# Ethernet.net
KiCad netlist of a schematic drawn in Altium Designer
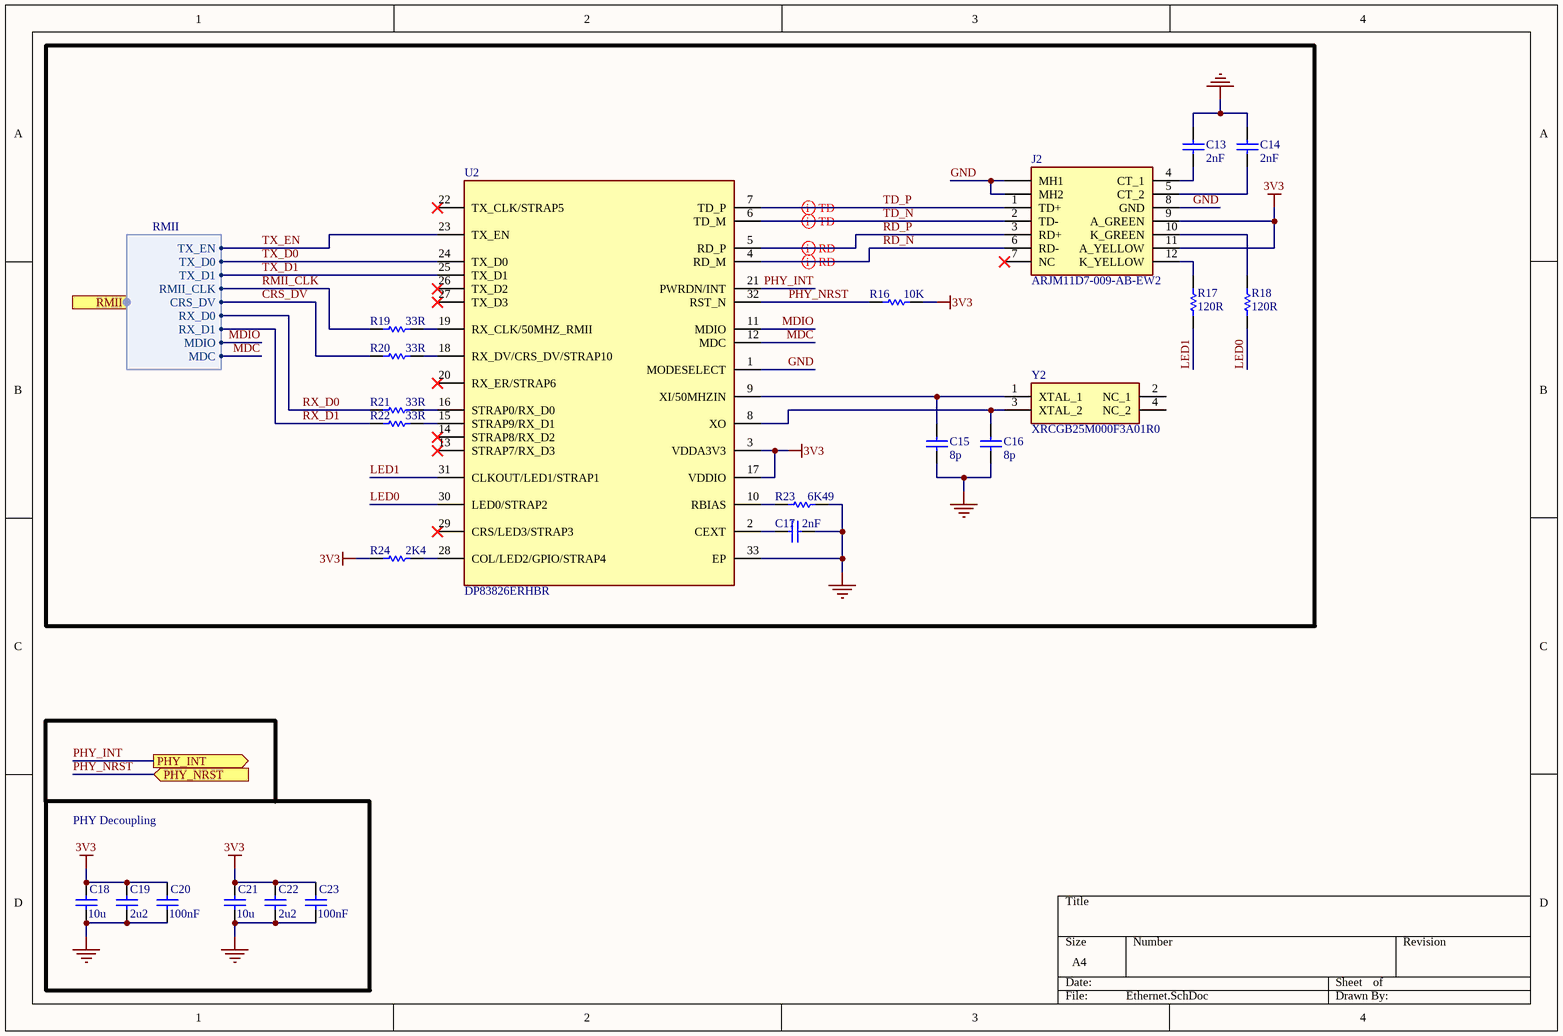
[diagram p0: Ethernet.SchDoc]

(export (version "E")
  (design (tool "Eeschema 10.0.6"))
  (components
    (comp (ref "C13")
      (value "2nF")
      (footprint "0603")
      (description "Capacitor 50V \r\n0603")
      (libsource (lib "Schlib1") (part "C0603C202J5GACTU"))
    )
    (comp (ref "C14")
      (value "2nF")
      (footprint "0603")
      (description "Capacitor 50V \r\n0603")
      (libsource (lib "Schlib1") (part "C0603C202J5GACTU"))
    )
    (comp (ref "C15")
      (value "8p")
      (footprint "0603")
      (description "Capacitor 25V \r\n0603")
      (libsource (lib "Schlib1") (part "06033A8R0DAT2A"))
    )
    (comp (ref "C16")
      (value "8p")
      (footprint "0603")
      (description "Capacitor 25V \r\n0603")
      (libsource (lib "Schlib1") (part "06033A8R0DAT2A"))
    )
    (comp (ref "C17")
      (value "2nF")
      (footprint "0603")
      (description "Capacitor 50V \r\n0603")
      (libsource (lib "Schlib1") (part "C0603C202J5GACTU"))
    )
    (comp (ref "C18")
      (value "10u")
      (footprint "1206")
      (description "Capacitor 50V\r\n1206")
      (libsource (lib "Schlib1") (part "C1206C106K3PACTU"))
    )
    (comp (ref "C19")
      (value "2u2")
      (footprint "1206")
      (description "Capacitor 50V\r\n1206")
      (libsource (lib "Schlib1") (part "C1206C225K5RACAUTO7210"))
    )
    (comp (ref "C20")
      (value "100nF")
      (footprint "0603")
      (description "Capacitor 100V \r\n0603")
      (libsource (lib "Schlib1") (part "C0603C104K1RACAUTO"))
    )
    (comp (ref "C21")
      (value "10u")
      (footprint "1206")
      (description "Capacitor 50V\r\n1206")
      (libsource (lib "Schlib1") (part "C1206C106K3PACTU"))
    )
    (comp (ref "C22")
      (value "2u2")
      (footprint "1206")
      (description "Capacitor 50V\r\n1206")
      (libsource (lib "Schlib1") (part "C1206C225K5RACAUTO7210"))
    )
    (comp (ref "C23")
      (value "100nF")
      (footprint "0603")
      (description "Capacitor 100V \r\n0603")
      (libsource (lib "Schlib1") (part "C0603C104K1RACAUTO"))
    )
    (comp (ref "J2")
      (value "ARJM11D7-009-AB-EW2")
      (footprint "ARJM11D7009ABEW2")
      (description "Connector")
      (fields (field (name "MOUSER PART NUMBER") "815-RJM11D7009ABEW2"))
      (libsource (lib "Schlib1") (part "ARJM11D7-009-AB-EW2"))
    )
    (comp (ref "R16")
      (value "10K")
      (footprint "0603")
      (description "Resistor 0.1W")
      (libsource (lib "Schlib1") (part "CRCW060310K0FKEA"))
    )
    (comp (ref "R17")
      (value "120R")
      (footprint "0603")
      (description "Resistor 0.1W")
      (libsource (lib "Schlib1") (part "CRCW0603120RFKEA"))
    )
    (comp (ref "R18")
      (value "120R")
      (footprint "0603")
      (description "Resistor 0.1W")
      (libsource (lib "Schlib1") (part "CRCW0603120RFKEA"))
    )
    (comp (ref "R19")
      (value "33R")
      (footprint "0603")
      (description "Resistor 0.1W")
      (libsource (lib "Schlib1") (part "CRCW060333R0FKEA"))
    )
    (comp (ref "R20")
      (value "33R")
      (footprint "0603")
      (description "Resistor 0.1W")
      (libsource (lib "Schlib1") (part "CRCW060333R0FKEA"))
    )
    (comp (ref "R21")
      (value "33R")
      (footprint "0603")
      (description "Resistor 0.1W")
      (libsource (lib "Schlib1") (part "CRCW060333R0FKEA"))
    )
    (comp (ref "R22")
      (value "33R")
      (footprint "0603")
      (description "Resistor 0.1W")
      (libsource (lib "Schlib1") (part "CRCW060333R0FKEA"))
    )
    (comp (ref "R23")
      (value "6K49")
      (footprint "0603")
      (description "Resistor 0.1W")
      (libsource (lib "Schlib1") (part "CRCW06036K49FKEA"))
    )
    (comp (ref "R24")
      (value "2K4")
      (footprint "0603")
      (description "Resistor 0.1W")
      (libsource (lib "Schlib1") (part "CRCW06032K40FKEA"))
    )
    (comp (ref "U2")
      (value "DP83826ERHBR")
      (footprint "SamacSys:QFN50P500X500X100-33N-D")
      (description "Integrated Circuit")
      (fields (field (name "MOUSER PART NUMBER") "595-DP83826ERHBR"))
      (libsource (lib "Schlib1") (part "DP83826ERHBR"))
    )
    (comp (ref "Y2")
      (value "XRCGB25M000F3A01R0")
      (footprint "XRCGB")
      (description "Crystal or Oscillator")
      (fields (field (name "MOUSER PART NUMBER") "81-XRCGB25M000F3A01R"))
      (libsource (lib "Schlib1") (part "XRCGB25M000F3A01R0"))
    )
  )
  (nets
    (net (code "2") (name "/CRS_DV") (class "Default")
      (node (ref "R20") (pin "1") (pinfunction "1_1") (pintype "passive"))
    )
    (net (code "3") (name "/LED0") (class "Default")
      (node (ref "R18") (pin "1") (pinfunction "1_1") (pintype "passive"))
      (node (ref "U2") (pin "30") (pinfunction "LED0/STRAP2_30") (pintype "passive"))
    )
    (net (code "4") (name "/LED1") (class "Default")
      (node (ref "R17") (pin "1") (pinfunction "1_1") (pintype "passive"))
      (node (ref "U2") (pin "31") (pinfunction "CLKOUT/LED1/STRAP1_31") (pintype "passive"))
    )
    (net (code "5") (name "/MDC") (class "Default")
      (node (ref "U2") (pin "12") (pinfunction "MDC_12") (pintype "passive"))
    )
    (net (code "6") (name "/MDIO") (class "Default")
      (node (ref "U2") (pin "11") (pinfunction "MDIO_11") (pintype "passive"))
    )
    (net (code "7") (name "/PHY_INT") (class "Default")
      (node (ref "U2") (pin "21") (pinfunction "PWRDN/INT_21") (pintype "passive"))
    )
    (net (code "8") (name "/PHY_NRST") (class "Default")
      (node (ref "R16") (pin "1") (pinfunction "1_1") (pintype "passive"))
      (node (ref "U2") (pin "32") (pinfunction "RST_N_32") (pintype "passive"))
    )
    (net (code "9") (name "/RD_N") (class "Default")
      (node (ref "J2") (pin "6") (pinfunction "RD-_6") (pintype "passive"))
      (node (ref "U2") (pin "4") (pinfunction "RD_M_4") (pintype "passive"))
    )
    (net (code "10") (name "/RD_P") (class "Default")
      (node (ref "J2") (pin "3") (pinfunction "RD+_3") (pintype "passive"))
      (node (ref "U2") (pin "5") (pinfunction "RD_P_5") (pintype "passive"))
    )
    (net (code "11") (name "/RMII_CLK") (class "Default")
      (node (ref "R19") (pin "1") (pinfunction "1_1") (pintype "passive"))
    )
    (net (code "12") (name "/RX_D0") (class "Default")
      (node (ref "R21") (pin "1") (pinfunction "1_1") (pintype "passive"))
    )
    (net (code "13") (name "/RX_D1") (class "Default")
      (node (ref "R22") (pin "1") (pinfunction "1_1") (pintype "passive"))
    )
    (net (code "14") (name "/TD_N") (class "Default")
      (node (ref "J2") (pin "2") (pinfunction "TD-_2") (pintype "passive"))
      (node (ref "U2") (pin "6") (pinfunction "TD_M_6") (pintype "passive"))
    )
    (net (code "15") (name "/TD_P") (class "Default")
      (node (ref "J2") (pin "1") (pinfunction "TD+_1") (pintype "passive"))
      (node (ref "U2") (pin "7") (pinfunction "TD_P_7") (pintype "passive"))
    )
    (net (code "16") (name "/TX_D0") (class "Default")
      (node (ref "U2") (pin "24") (pinfunction "TX_D0_24") (pintype "passive"))
    )
    (net (code "17") (name "/TX_D1") (class "Default")
      (node (ref "U2") (pin "25") (pinfunction "TX_D1_25") (pintype "passive"))
    )
    (net (code "18") (name "/TX_EN") (class "Default")
      (node (ref "U2") (pin "23") (pinfunction "TX_EN_23") (pintype "passive"))
    )
    (net (code "20") (name "3V3") (class "Default")
      (node (ref "C18") (pin "2") (pinfunction "2_2") (pintype "passive"))
      (node (ref "C19") (pin "2") (pinfunction "2_2") (pintype "passive"))
      (node (ref "C20") (pin "2") (pinfunction "2_2") (pintype "passive"))
      (node (ref "C21") (pin "2") (pinfunction "2_2") (pintype "passive"))
      (node (ref "C22") (pin "2") (pinfunction "2_2") (pintype "passive"))
      (node (ref "C23") (pin "2") (pinfunction "2_2") (pintype "passive"))
      (node (ref "J2") (pin "11") (pinfunction "A_YELLOW_11") (pintype "passive"))
      (node (ref "J2") (pin "9") (pinfunction "A_GREEN_9") (pintype "passive"))
      (node (ref "R16") (pin "2") (pinfunction "2_2") (pintype "passive"))
      (node (ref "R24") (pin "1") (pinfunction "1_1") (pintype "passive"))
      (node (ref "U2") (pin "17") (pinfunction "VDDIO_17") (pintype "passive"))
      (node (ref "U2") (pin "3") (pinfunction "VDDA3V3_3") (pintype "passive"))
    )
    (net (code "21") (name "GND") (class "Default")
      (node (ref "C13") (pin "2") (pinfunction "2_2") (pintype "passive"))
      (node (ref "C14") (pin "2") (pinfunction "2_2") (pintype "passive"))
      (node (ref "C15") (pin "1") (pinfunction "1_1") (pintype "passive"))
      (node (ref "C16") (pin "1") (pinfunction "1_1") (pintype "passive"))
      (node (ref "C17") (pin "2") (pinfunction "2_2") (pintype "passive"))
      (node (ref "C18") (pin "1") (pinfunction "1_1") (pintype "passive"))
      (node (ref "C19") (pin "1") (pinfunction "1_1") (pintype "passive"))
      (node (ref "C20") (pin "1") (pinfunction "1_1") (pintype "passive"))
      (node (ref "C21") (pin "1") (pinfunction "1_1") (pintype "passive"))
      (node (ref "C22") (pin "1") (pinfunction "1_1") (pintype "passive"))
      (node (ref "C23") (pin "1") (pinfunction "1_1") (pintype "passive"))
      (node (ref "J2") (pin "8") (pinfunction "GND_8") (pintype "passive"))
      (node (ref "J2") (pin "MH1") (pinfunction "MH1_MH1") (pintype "passive"))
      (node (ref "J2") (pin "MH2") (pinfunction "MH2_MH2") (pintype "passive"))
      (node (ref "R23") (pin "2") (pinfunction "2_2") (pintype "passive"))
      (node (ref "U2") (pin "1") (pinfunction "MODESELECT_1") (pintype "passive"))
      (node (ref "U2") (pin "33") (pinfunction "EP_33") (pintype "passive"))
    )
    (net (code "22") (name "Net-(J2-CT_1)") (class "Default")
      (node (ref "C13") (pin "1") (pinfunction "1_1") (pintype "passive"))
      (node (ref "J2") (pin "4") (pinfunction "CT_1_4") (pintype "passive"))
    )
    (net (code "23") (name "Net-(J2-CT_2)") (class "Default")
      (node (ref "C14") (pin "1") (pinfunction "1_1") (pintype "passive"))
      (node (ref "J2") (pin "5") (pinfunction "CT_2_5") (pintype "passive"))
    )
    (net (code "24") (name "Net-(J2-K_GREEN)") (class "Default")
      (node (ref "J2") (pin "10") (pinfunction "K_GREEN_10") (pintype "passive"))
      (node (ref "R18") (pin "2") (pinfunction "2_2") (pintype "passive"))
    )
    (net (code "25") (name "Net-(J2-K_YELLOW)") (class "Default")
      (node (ref "J2") (pin "12") (pinfunction "K_YELLOW_12") (pintype "passive"))
      (node (ref "R17") (pin "2") (pinfunction "2_2") (pintype "passive"))
    )
    (net (code "26") (name "Net-(U2-CEXT)") (class "Default")
      (node (ref "C17") (pin "1") (pinfunction "1_1") (pintype "passive"))
      (node (ref "U2") (pin "2") (pinfunction "CEXT_2") (pintype "passive"))
    )
    (net (code "27") (name "Net-(U2-COL{slash}LED2{slash}GPIO{slash}STRAP4)") (class "Default")
      (node (ref "R24") (pin "2") (pinfunction "2_2") (pintype "passive"))
      (node (ref "U2") (pin "28") (pinfunction "COL/LED2/GPIO/STRAP4_28") (pintype "passive"))
    )
    (net (code "28") (name "Net-(U2-RBIAS)") (class "Default")
      (node (ref "R23") (pin "1") (pinfunction "1_1") (pintype "passive"))
      (node (ref "U2") (pin "10") (pinfunction "RBIAS_10") (pintype "passive"))
    )
    (net (code "29") (name "Net-(U2-RX_CLK{slash}50MHZ_RMII)") (class "Default")
      (node (ref "R19") (pin "2") (pinfunction "2_2") (pintype "passive"))
      (node (ref "U2") (pin "19") (pinfunction "RX_CLK/50MHZ_RMII_19") (pintype "passive"))
    )
    (net (code "30") (name "Net-(U2-RX_DV{slash}CRS_DV{slash}STRAP10)") (class "Default")
      (node (ref "R20") (pin "2") (pinfunction "2_2") (pintype "passive"))
      (node (ref "U2") (pin "18") (pinfunction "RX_DV/CRS_DV/STRAP10_18") (pintype "passive"))
    )
    (net (code "31") (name "Net-(U2-STRAP0{slash}RX_D0)") (class "Default")
      (node (ref "R21") (pin "2") (pinfunction "2_2") (pintype "passive"))
      (node (ref "U2") (pin "16") (pinfunction "STRAP0/RX_D0_16") (pintype "passive"))
    )
    (net (code "32") (name "Net-(U2-STRAP9{slash}RX_D1)") (class "Default")
      (node (ref "R22") (pin "2") (pinfunction "2_2") (pintype "passive"))
      (node (ref "U2") (pin "15") (pinfunction "STRAP9/RX_D1_15") (pintype "passive"))
    )
    (net (code "33") (name "Net-(U2-XI{slash}50MHZIN)") (class "Default")
      (node (ref "C15") (pin "2") (pinfunction "2_2") (pintype "passive"))
      (node (ref "U2") (pin "9") (pinfunction "XI/50MHZIN_9") (pintype "passive"))
      (node (ref "Y2") (pin "1") (pinfunction "XTAL_1_1") (pintype "passive"))
    )
    (net (code "34") (name "Net-(U2-XO)") (class "Default")
      (node (ref "C16") (pin "2") (pinfunction "2_2") (pintype "passive"))
      (node (ref "U2") (pin "8") (pinfunction "XO_8") (pintype "passive"))
      (node (ref "Y2") (pin "3") (pinfunction "XTAL_2_3") (pintype "passive"))
    )
    (net (code "35") (name "unconnected-(J2-NC-Pad7)") (class "Default")
      (node (ref "J2") (pin "7") (pinfunction "NC_7") (pintype "passive+no_connect"))
    )
    (net (code "36") (name "unconnected-(U2-CRS{slash}LED3{slash}STRAP3-Pad29)") (class "Default")
      (node (ref "U2") (pin "29") (pinfunction "CRS/LED3/STRAP3_29") (pintype "passive+no_connect"))
    )
    (net (code "37") (name "unconnected-(U2-RX_ER{slash}STRAP6-Pad20)") (class "Default")
      (node (ref "U2") (pin "20") (pinfunction "RX_ER/STRAP6_20") (pintype "passive+no_connect"))
    )
    (net (code "38") (name "unconnected-(U2-STRAP7{slash}RX_D3-Pad13)") (class "Default")
      (node (ref "U2") (pin "13") (pinfunction "STRAP7/RX_D3_13") (pintype "passive+no_connect"))
    )
    (net (code "39") (name "unconnected-(U2-STRAP8{slash}RX_D2-Pad14)") (class "Default")
      (node (ref "U2") (pin "14") (pinfunction "STRAP8/RX_D2_14") (pintype "passive+no_connect"))
    )
    (net (code "40") (name "unconnected-(U2-TX_CLK{slash}STRAP5-Pad22)") (class "Default")
      (node (ref "U2") (pin "22") (pinfunction "TX_CLK/STRAP5_22") (pintype "passive+no_connect"))
    )
    (net (code "41") (name "unconnected-(U2-TX_D2-Pad26)") (class "Default")
      (node (ref "U2") (pin "26") (pinfunction "TX_D2_26") (pintype "passive+no_connect"))
    )
    (net (code "42") (name "unconnected-(U2-TX_D3-Pad27)") (class "Default")
      (node (ref "U2") (pin "27") (pinfunction "TX_D3_27") (pintype "passive+no_connect"))
    )
    (net (code "43") (name "unconnected-(Y2-NC_1-Pad2)") (class "Default")
      (node (ref "Y2") (pin "2") (pinfunction "NC_1_2") (pintype "passive"))
    )
    (net (code "44") (name "unconnected-(Y2-NC_2-Pad4)") (class "Default")
      (node (ref "Y2") (pin "4") (pinfunction "NC_2_4") (pintype "passive"))
    )
  )
)
